# Sensor-amplification_V4.net
KiCad netlist of a schematic drawn in EAGLE
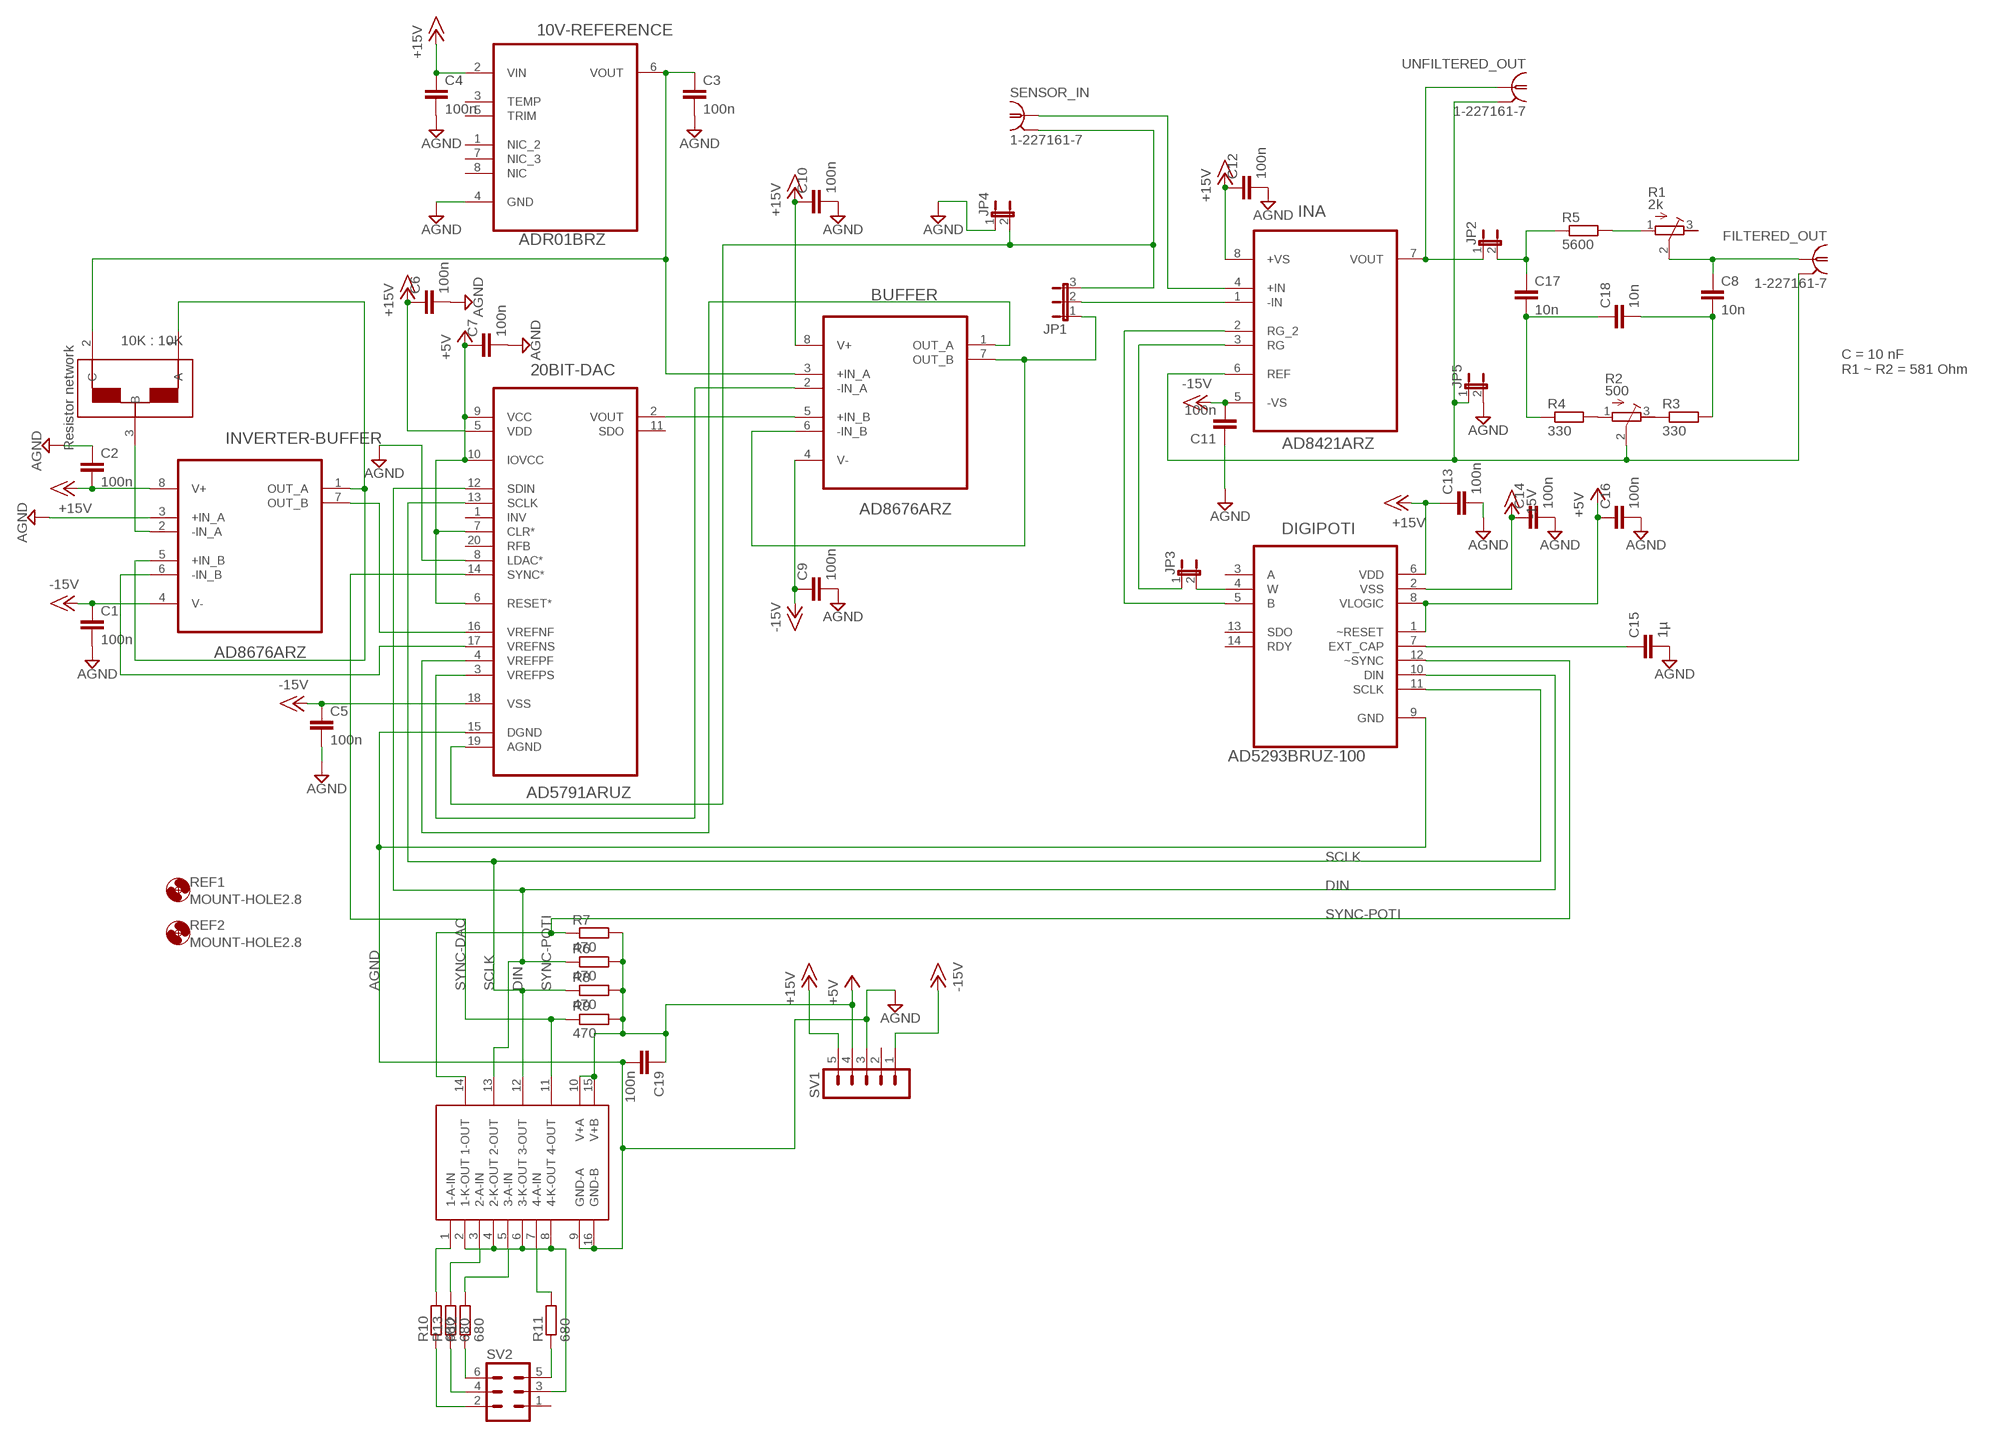
[diagram p0: schematic, sheet 1]

(export (version "E")
  (design (tool "Eeschema 10.0.6"))
  (components
    (comp (ref "10V-REFERENCE")
      (value "ADR01BRZ")
      (footprint "eagle-import:SOIC127P600X175-8N")
      (libsource (lib "eagle-import") (part "ADR01BRZ"))
    )
    (comp (ref "20BIT-DAC")
      (value "AD5791ARUZ")
      (footprint "eagle-import:SOP65P640X120-20N")
      (libsource (lib "eagle-import") (part "AD5791ARUZ"))
    )
    (comp (ref "BUFFER")
      (value "AD8676ARZ")
      (footprint "eagle-import:SOIC127P600X175-8N")
      (libsource (lib "eagle-import") (part "AD8676ARZ"))
    )
    (comp (ref "C1")
      (value "100n")
      (footprint "eagle-import:C0603")
      (libsource (lib "eagle-import") (part "C-EUC0603"))
    )
    (comp (ref "C2")
      (value "100n")
      (footprint "eagle-import:C0603")
      (libsource (lib "eagle-import") (part "C-EUC0603"))
    )
    (comp (ref "C3")
      (value "100n")
      (footprint "eagle-import:C0603")
      (libsource (lib "eagle-import") (part "C-EUC0603"))
    )
    (comp (ref "C4")
      (value "100n")
      (footprint "eagle-import:C0603")
      (libsource (lib "eagle-import") (part "C-EUC0603"))
    )
    (comp (ref "C5")
      (value "100n")
      (footprint "eagle-import:C0603")
      (libsource (lib "eagle-import") (part "C-EUC0603"))
    )
    (comp (ref "C6")
      (value "100n")
      (footprint "eagle-import:C0603")
      (libsource (lib "eagle-import") (part "C-EUC0603"))
    )
    (comp (ref "C7")
      (value "100n")
      (footprint "eagle-import:C0603")
      (libsource (lib "eagle-import") (part "C-EUC0603"))
    )
    (comp (ref "C8")
      (value "10n")
      (footprint "eagle-import:C0805")
      (libsource (lib "eagle-import") (part "C-EUC0805"))
    )
    (comp (ref "C9")
      (value "100n")
      (footprint "eagle-import:C0603")
      (libsource (lib "eagle-import") (part "C-EUC0603"))
    )
    (comp (ref "C10")
      (value "100n")
      (footprint "eagle-import:C0603")
      (libsource (lib "eagle-import") (part "C-EUC0603"))
    )
    (comp (ref "C11")
      (value "100n")
      (footprint "eagle-import:C0603")
      (libsource (lib "eagle-import") (part "C-EUC0603"))
    )
    (comp (ref "C12")
      (value "100n")
      (footprint "eagle-import:C0603")
      (libsource (lib "eagle-import") (part "C-EUC0603"))
    )
    (comp (ref "C13")
      (value "100n")
      (footprint "eagle-import:C0603")
      (libsource (lib "eagle-import") (part "C-EUC0603"))
    )
    (comp (ref "C14")
      (value "100n")
      (footprint "eagle-import:C0603")
      (libsource (lib "eagle-import") (part "C-EUC0603"))
    )
    (comp (ref "C15")
      (value "1µ")
      (footprint "eagle-import:C0603")
      (libsource (lib "eagle-import") (part "C-EUC0603"))
    )
    (comp (ref "C16")
      (value "100n")
      (footprint "eagle-import:C0603")
      (libsource (lib "eagle-import") (part "C-EUC0603"))
    )
    (comp (ref "C17")
      (value "10n")
      (footprint "eagle-import:C0805")
      (libsource (lib "eagle-import") (part "C-EUC0805"))
    )
    (comp (ref "C18")
      (value "10n")
      (footprint "eagle-import:C0805")
      (libsource (lib "eagle-import") (part "C-EUC0805"))
    )
    (comp (ref "C19")
      (value "100n")
      (footprint "eagle-import:C0603")
      (libsource (lib "eagle-import") (part "C-EUC0603"))
    )
    (comp (ref "DIGIPOTI")
      (value "AD5293BRUZ-100")
      (footprint "eagle-import:SOP65P640X120-14N")
      (libsource (lib "eagle-import") (part "AD5293BRUZ-100"))
    )
    (comp (ref "FILTERED_OUT")
      (value "1-227161-7")
      (footprint "eagle-import:AMP_227161")
      (fields (field (name "MF") "TYCO ELECTRONICS"))
      (libsource (lib "eagle-import") (part "?2271611--7"))
    )
    (comp (ref "INA")
      (value "AD8421ARZ")
      (footprint "eagle-import:SOIC127P600X175-8N")
      (libsource (lib "eagle-import") (part "AD8421ARZ"))
    )
    (comp (ref "INVERTER-BUFFER")
      (value "AD8676ARZ")
      (footprint "eagle-import:SOIC127P600X175-8N")
      (libsource (lib "eagle-import") (part "AD8676ARZ"))
    )
    (comp (ref "JP1")
      (value "JP2E")
      (footprint "eagle-import:JP2")
      (libsource (lib "eagle-import") (part "JP2E"))
    )
    (comp (ref "JP2")
      (value "JP1E")
      (footprint "eagle-import:JP1")
      (libsource (lib "eagle-import") (part "JP1E"))
    )
    (comp (ref "JP3")
      (value "JP1E")
      (footprint "eagle-import:JP1")
      (libsource (lib "eagle-import") (part "JP1E"))
    )
    (comp (ref "JP4")
      (value "JP1E")
      (footprint "eagle-import:JP1")
      (libsource (lib "eagle-import") (part "JP1E"))
    )
    (comp (ref "JP5")
      (value "JP1E")
      (footprint "eagle-import:JP1")
      (libsource (lib "eagle-import") (part "JP1E"))
    )
    (comp (ref "OPTOCOUPLER")
      (value "ACSL-6400")
      (footprint "eagle-import:SO16")
      (libsource (lib "eagle-import") (part "ACSL-6400"))
    )
    (comp (ref "R1")
      (value "2k")
      (footprint "eagle-import:RTRIM64W")
      (libsource (lib "eagle-import") (part "R-TRIMM64W"))
    )
    (comp (ref "R2")
      (value "500")
      (footprint "eagle-import:RTRIM64W")
      (libsource (lib "eagle-import") (part "R-TRIMM64W"))
    )
    (comp (ref "R3")
      (value "330")
      (footprint "eagle-import:M1206")
      (libsource (lib "eagle-import") (part "R-EU_M1206"))
    )
    (comp (ref "R4")
      (value "330")
      (footprint "eagle-import:M1206")
      (libsource (lib "eagle-import") (part "R-EU_M1206"))
    )
    (comp (ref "R5")
      (value "5600")
      (footprint "eagle-import:M1206")
      (libsource (lib "eagle-import") (part "R-EU_M1206"))
    )
    (comp (ref "R6")
      (value "470")
      (footprint "eagle-import:M1206")
      (libsource (lib "eagle-import") (part "R-EU_M1206"))
    )
    (comp (ref "R7")
      (value "470")
      (footprint "eagle-import:M1206")
      (libsource (lib "eagle-import") (part "R-EU_M1206"))
    )
    (comp (ref "R8")
      (value "470")
      (footprint "eagle-import:M1206")
      (libsource (lib "eagle-import") (part "R-EU_M1206"))
    )
    (comp (ref "R9")
      (value "470")
      (footprint "eagle-import:M1206")
      (libsource (lib "eagle-import") (part "R-EU_M1206"))
    )
    (comp (ref "R10")
      (value "680")
      (footprint "eagle-import:M1206")
      (libsource (lib "eagle-import") (part "R-EU_M1206"))
    )
    (comp (ref "R11")
      (value "680")
      (footprint "eagle-import:M1206")
      (libsource (lib "eagle-import") (part "R-EU_M1206"))
    )
    (comp (ref "R12")
      (value "680")
      (footprint "eagle-import:M1206")
      (libsource (lib "eagle-import") (part "R-EU_M1206"))
    )
    (comp (ref "R13")
      (value "680")
      (footprint "eagle-import:M1206")
      (libsource (lib "eagle-import") (part "R-EU_M1206"))
    )
    (comp (ref "R20")
      (value "MPMT2001AT5")
      (footprint "eagle-import:SOT23")
      (libsource (lib "eagle-import") (part "MPMT2001AT5"))
    )
    (comp (ref "REF1")
      (value "MOUNT-HOLE2.8")
      (footprint "eagle-import:2,8")
      (libsource (lib "eagle-import") (part "MOUNT-HOLE2.8"))
    )
    (comp (ref "REF2")
      (value "MOUNT-HOLE2.8")
      (footprint "eagle-import:2,8")
      (libsource (lib "eagle-import") (part "MOUNT-HOLE2.8"))
    )
    (comp (ref "SENSOR_IN")
      (value "1-227161-7")
      (footprint "eagle-import:AMP_227161")
      (fields (field (name "MF") "TYCO ELECTRONICS"))
      (libsource (lib "eagle-import") (part "?2271611--7"))
    )
    (comp (ref "SV1")
      (value "MA05-1")
      (footprint "eagle-import:MA05-1")
      (libsource (lib "eagle-import") (part "MA05-1"))
    )
    (comp (ref "SV2")
      (value "MA03-2")
      (footprint "eagle-import:MA03-2")
      (libsource (lib "eagle-import") (part "MA03-2"))
    )
    (comp (ref "UNFILTERED_OUT")
      (value "1-227161-7")
      (footprint "eagle-import:AMP_227161")
      (fields (field (name "MF") "TYCO ELECTRONICS"))
      (libsource (lib "eagle-import") (part "?2271611--7"))
    )
  )
  (nets
    (net (code "1") (name "+5V") (class "Default")
      (node (ref "20BIT-DAC") (pin "10") (pinfunction "IOVCC_10") (pintype "power_in"))
      (node (ref "20BIT-DAC") (pin "6") (pinfunction "RESET*_6") (pintype "input"))
      (node (ref "20BIT-DAC") (pin "7") (pinfunction "CLR*_7") (pintype "input"))
      (node (ref "20BIT-DAC") (pin "9") (pinfunction "VCC_9") (pintype "power_in"))
      (node (ref "C16") (pin "1") (pinfunction "1_1") (pintype "passive"))
      (node (ref "C19") (pin "1") (pinfunction "1_1") (pintype "passive"))
      (node (ref "C7") (pin "1") (pinfunction "1_1") (pintype "passive"))
      (node (ref "DIGIPOTI") (pin "1") (pinfunction "~{RESET}_1") (pintype "input"))
      (node (ref "DIGIPOTI") (pin "8") (pinfunction "VLOGIC_8") (pintype "power_in"))
      (node (ref "OPTOCOUPLER") (pin "10") (pinfunction "V+A_10") (pintype "power_in"))
      (node (ref "OPTOCOUPLER") (pin "15") (pinfunction "V+B_15") (pintype "power_in"))
      (node (ref "R6") (pin "2") (pinfunction "2_2") (pintype "passive"))
      (node (ref "R7") (pin "2") (pinfunction "2_2") (pintype "passive"))
      (node (ref "R8") (pin "2") (pinfunction "2_2") (pintype "passive"))
      (node (ref "R9") (pin "2") (pinfunction "2_2") (pintype "passive"))
      (node (ref "SV1") (pin "4") (pinfunction "4_4") (pintype "passive"))
    )
    (net (code "2") (name "+15V") (class "Default")
      (node (ref "10V-REFERENCE") (pin "2") (pinfunction "VIN_2") (pintype "input"))
      (node (ref "20BIT-DAC") (pin "5") (pinfunction "VDD_5") (pintype "power_in"))
      (node (ref "BUFFER") (pin "8") (pinfunction "V+_8") (pintype "power_in"))
      (node (ref "C10") (pin "1") (pinfunction "1_1") (pintype "passive"))
      (node (ref "C12") (pin "1") (pinfunction "1_1") (pintype "passive"))
      (node (ref "C13") (pin "1") (pinfunction "1_1") (pintype "passive"))
      (node (ref "C2") (pin "2") (pinfunction "2_2") (pintype "passive"))
      (node (ref "C4") (pin "1") (pinfunction "1_1") (pintype "passive"))
      (node (ref "C6") (pin "1") (pinfunction "1_1") (pintype "passive"))
      (node (ref "DIGIPOTI") (pin "6") (pinfunction "VDD_6") (pintype "power_in"))
      (node (ref "INA") (pin "8") (pinfunction "+VS_8") (pintype "power_in"))
      (node (ref "INVERTER-BUFFER") (pin "8") (pinfunction "V+_8") (pintype "power_in"))
      (node (ref "SV1") (pin "5") (pinfunction "5_5") (pintype "passive"))
    )
    (net (code "3") (name "-15V") (class "Default")
      (node (ref "20BIT-DAC") (pin "18") (pinfunction "VSS_18") (pintype "power_in"))
      (node (ref "BUFFER") (pin "4") (pinfunction "V-_4") (pintype "power_in"))
      (node (ref "C1") (pin "1") (pinfunction "1_1") (pintype "passive"))
      (node (ref "C11") (pin "2") (pinfunction "2_2") (pintype "passive"))
      (node (ref "C14") (pin "1") (pinfunction "1_1") (pintype "passive"))
      (node (ref "C5") (pin "1") (pinfunction "1_1") (pintype "passive"))
      (node (ref "C9") (pin "1") (pinfunction "1_1") (pintype "passive"))
      (node (ref "DIGIPOTI") (pin "2") (pinfunction "VSS_2") (pintype "power_in"))
      (node (ref "INA") (pin "5") (pinfunction "-VS_5") (pintype "power_in"))
      (node (ref "INVERTER-BUFFER") (pin "4") (pinfunction "V-_4") (pintype "power_in"))
      (node (ref "SV1") (pin "1") (pinfunction "1_1") (pintype "passive"))
    )
    (net (code "4") (name "/DIN") (class "Default")
      (node (ref "20BIT-DAC") (pin "12") (pinfunction "SDIN_12") (pintype "input"))
      (node (ref "DIGIPOTI") (pin "10") (pinfunction "DIN_10") (pintype "input"))
      (node (ref "OPTOCOUPLER") (pin "13") (pinfunction "2-OUT_13") (pintype "output"))
      (node (ref "R6") (pin "1") (pinfunction "1_1") (pintype "passive"))
    )
    (net (code "5") (name "/SCLK") (class "Default")
      (node (ref "20BIT-DAC") (pin "13") (pinfunction "SCLK_13") (pintype "input"))
      (node (ref "DIGIPOTI") (pin "11") (pinfunction "SCLK_11") (pintype "input"))
      (node (ref "OPTOCOUPLER") (pin "12") (pinfunction "3-OUT_12") (pintype "output"))
      (node (ref "R8") (pin "1") (pinfunction "1_1") (pintype "passive"))
    )
    (net (code "6") (name "/SYNC-DAC") (class "Default")
      (node (ref "20BIT-DAC") (pin "14") (pinfunction "SYNC*_14") (pintype "input"))
      (node (ref "OPTOCOUPLER") (pin "11") (pinfunction "4-OUT_11") (pintype "output"))
      (node (ref "R9") (pin "1") (pinfunction "1_1") (pintype "passive"))
    )
    (net (code "7") (name "/SYNC-POTI") (class "Default")
      (node (ref "DIGIPOTI") (pin "12") (pinfunction "~{SYNC}_12") (pintype "input"))
      (node (ref "OPTOCOUPLER") (pin "14") (pinfunction "1-OUT_14") (pintype "output"))
      (node (ref "R7") (pin "1") (pinfunction "1_1") (pintype "passive"))
    )
    (net (code "8") (name "AGND") (class "Default")
      (node (ref "10V-REFERENCE") (pin "4") (pinfunction "GND_4") (pintype "passive"))
      (node (ref "20BIT-DAC") (pin "15") (pinfunction "DGND_15") (pintype "passive"))
      (node (ref "20BIT-DAC") (pin "8") (pinfunction "LDAC*_8") (pintype "input"))
      (node (ref "C1") (pin "2") (pinfunction "2_2") (pintype "passive"))
      (node (ref "C10") (pin "2") (pinfunction "2_2") (pintype "passive"))
      (node (ref "C11") (pin "1") (pinfunction "1_1") (pintype "passive"))
      (node (ref "C12") (pin "2") (pinfunction "2_2") (pintype "passive"))
      (node (ref "C13") (pin "2") (pinfunction "2_2") (pintype "passive"))
      (node (ref "C14") (pin "2") (pinfunction "2_2") (pintype "passive"))
      (node (ref "C15") (pin "2") (pinfunction "2_2") (pintype "passive"))
      (node (ref "C16") (pin "2") (pinfunction "2_2") (pintype "passive"))
      (node (ref "C19") (pin "2") (pinfunction "2_2") (pintype "passive"))
      (node (ref "C2") (pin "1") (pinfunction "1_1") (pintype "passive"))
      (node (ref "C3") (pin "2") (pinfunction "2_2") (pintype "passive"))
      (node (ref "C4") (pin "2") (pinfunction "2_2") (pintype "passive"))
      (node (ref "C5") (pin "2") (pinfunction "2_2") (pintype "passive"))
      (node (ref "C6") (pin "2") (pinfunction "2_2") (pintype "passive"))
      (node (ref "C7") (pin "2") (pinfunction "2_2") (pintype "passive"))
      (node (ref "C9") (pin "2") (pinfunction "2_2") (pintype "passive"))
      (node (ref "DIGIPOTI") (pin "9") (pinfunction "GND_9") (pintype "passive"))
      (node (ref "INVERTER-BUFFER") (pin "3") (pinfunction "+IN_A_3") (pintype "input"))
      (node (ref "JP4") (pin "1") (pinfunction "1_1") (pintype "passive"))
      (node (ref "JP5") (pin "2") (pinfunction "2_2") (pintype "passive"))
      (node (ref "OPTOCOUPLER") (pin "16") (pinfunction "GND-B_16") (pintype "power_in"))
      (node (ref "OPTOCOUPLER") (pin "9") (pinfunction "GND-A_9") (pintype "power_in"))
      (node (ref "SV1") (pin "3") (pinfunction "3_3") (pintype "passive"))
    )
    (net (code "9") (name "Net-(10V-REFERENCE-VOUT)") (class "Default")
      (node (ref "10V-REFERENCE") (pin "6") (pinfunction "VOUT_6") (pintype "output"))
      (node (ref "BUFFER") (pin "3") (pinfunction "+IN_A_3") (pintype "input"))
      (node (ref "C3") (pin "1") (pinfunction "1_1") (pintype "passive"))
      (node (ref "R20") (pin "2") (pinfunction "C_2") (pintype "passive"))
    )
    (net (code "10") (name "Net-(20BIT-DAC-AGND)") (class "Default")
      (node (ref "20BIT-DAC") (pin "19") (pinfunction "AGND_19") (pintype "passive"))
      (node (ref "JP1") (pin "3") (pinfunction "3_3") (pintype "passive"))
      (node (ref "JP4") (pin "2") (pinfunction "2_2") (pintype "passive"))
      (node (ref "SENSOR_IN") (pin "2") (pinfunction "2_2") (pintype "passive"))
    )
    (net (code "11") (name "Net-(20BIT-DAC-VOUT)") (class "Default")
      (node (ref "20BIT-DAC") (pin "2") (pinfunction "VOUT_2") (pintype "output"))
      (node (ref "BUFFER") (pin "5") (pinfunction "+IN_B_5") (pintype "input"))
    )
    (net (code "12") (name "Net-(20BIT-DAC-VREFNF)") (class "Default")
      (node (ref "20BIT-DAC") (pin "16") (pinfunction "VREFNF_16") (pintype "input"))
      (node (ref "INVERTER-BUFFER") (pin "7") (pinfunction "OUT_B_7") (pintype "output"))
    )
    (net (code "13") (name "Net-(20BIT-DAC-VREFNS)") (class "Default")
      (node (ref "20BIT-DAC") (pin "17") (pinfunction "VREFNS_17") (pintype "input"))
      (node (ref "INVERTER-BUFFER") (pin "6") (pinfunction "-IN_B_6") (pintype "input"))
    )
    (net (code "14") (name "Net-(20BIT-DAC-VREFPF)") (class "Default")
      (node (ref "20BIT-DAC") (pin "4") (pinfunction "VREFPF_4") (pintype "input"))
      (node (ref "BUFFER") (pin "1") (pinfunction "OUT_A_1") (pintype "output"))
    )
    (net (code "15") (name "Net-(20BIT-DAC-VREFPS)") (class "Default")
      (node (ref "20BIT-DAC") (pin "3") (pinfunction "VREFPS_3") (pintype "input"))
      (node (ref "BUFFER") (pin "2") (pinfunction "-IN_A_2") (pintype "input"))
    )
    (net (code "16") (name "Net-(BUFFER--IN_B)") (class "Default")
      (node (ref "BUFFER") (pin "6") (pinfunction "-IN_B_6") (pintype "input"))
      (node (ref "BUFFER") (pin "7") (pinfunction "OUT_B_7") (pintype "output"))
      (node (ref "JP1") (pin "1") (pinfunction "1_1") (pintype "passive"))
    )
    (net (code "17") (name "Net-(C17-Pad1)") (class "Default")
      (node (ref "C17") (pin "1") (pinfunction "1_1") (pintype "passive"))
      (node (ref "JP2") (pin "2") (pinfunction "2_2") (pintype "passive"))
      (node (ref "R5") (pin "1") (pinfunction "1_1") (pintype "passive"))
    )
    (net (code "18") (name "Net-(C17-Pad2)") (class "Default")
      (node (ref "C17") (pin "2") (pinfunction "2_2") (pintype "passive"))
      (node (ref "C18") (pin "1") (pinfunction "1_1") (pintype "passive"))
      (node (ref "R4") (pin "1") (pinfunction "1_1") (pintype "passive"))
    )
    (net (code "19") (name "Net-(C18-Pad2)") (class "Default")
      (node (ref "C18") (pin "2") (pinfunction "2_2") (pintype "passive"))
      (node (ref "C8") (pin "2") (pinfunction "2_2") (pintype "passive"))
      (node (ref "R3") (pin "2") (pinfunction "2_2") (pintype "passive"))
    )
    (net (code "20") (name "Net-(DIGIPOTI-B)") (class "Default")
      (node (ref "DIGIPOTI") (pin "5") (pinfunction "B_5") (pintype "passive"))
      (node (ref "INA") (pin "2") (pinfunction "RG_2_2") (pintype "input"))
    )
    (net (code "21") (name "Net-(DIGIPOTI-EXT_CAP)") (class "Default")
      (node (ref "C15") (pin "1") (pinfunction "1_1") (pintype "passive"))
      (node (ref "DIGIPOTI") (pin "7") (pinfunction "EXT_CAP_7") (pintype "passive"))
    )
    (net (code "22") (name "Net-(DIGIPOTI-W)") (class "Default")
      (node (ref "DIGIPOTI") (pin "4") (pinfunction "W_4") (pintype "passive"))
      (node (ref "JP3") (pin "2") (pinfunction "2_2") (pintype "passive"))
    )
    (net (code "23") (name "Net-(INA-+IN)") (class "Default")
      (node (ref "INA") (pin "4") (pinfunction "+IN_4") (pintype "input"))
      (node (ref "SENSOR_IN") (pin "1") (pinfunction "1_1") (pintype "passive"))
    )
    (net (code "24") (name "Net-(INA--IN)") (class "Default")
      (node (ref "INA") (pin "1") (pinfunction "-IN_1") (pintype "input"))
      (node (ref "JP1") (pin "2") (pinfunction "2_2") (pintype "passive"))
    )
    (net (code "25") (name "Net-(INA-REF)") (class "Default")
      (node (ref "FILTERED_OUT") (pin "2") (pinfunction "2_2") (pintype "passive"))
      (node (ref "INA") (pin "6") (pinfunction "REF_6") (pintype "input"))
      (node (ref "JP5") (pin "1") (pinfunction "1_1") (pintype "passive"))
      (node (ref "R2") (pin "2") (pinfunction "S_2") (pintype "passive"))
      (node (ref "UNFILTERED_OUT") (pin "2") (pinfunction "2_2") (pintype "passive"))
    )
    (net (code "26") (name "Net-(INA-RG)") (class "Default")
      (node (ref "INA") (pin "3") (pinfunction "RG_3") (pintype "input"))
      (node (ref "JP3") (pin "1") (pinfunction "1_1") (pintype "passive"))
    )
    (net (code "27") (name "Net-(INA-VOUT)") (class "Default")
      (node (ref "INA") (pin "7") (pinfunction "VOUT_7") (pintype "output"))
      (node (ref "JP2") (pin "1") (pinfunction "1_1") (pintype "passive"))
      (node (ref "UNFILTERED_OUT") (pin "1") (pinfunction "1_1") (pintype "passive"))
    )
    (net (code "28") (name "Net-(INVERTER-BUFFER-+IN_B)") (class "Default")
      (node (ref "INVERTER-BUFFER") (pin "1") (pinfunction "OUT_A_1") (pintype "output"))
      (node (ref "INVERTER-BUFFER") (pin "5") (pinfunction "+IN_B_5") (pintype "input"))
      (node (ref "R20") (pin "1") (pinfunction "A_1") (pintype "passive"))
    )
    (net (code "29") (name "Net-(INVERTER-BUFFER--IN_A)") (class "Default")
      (node (ref "INVERTER-BUFFER") (pin "2") (pinfunction "-IN_A_2") (pintype "input"))
      (node (ref "R20") (pin "3") (pinfunction "B_3") (pintype "passive"))
    )
    (net (code "30") (name "Net-(OPTOCOUPLER-1-A-IN)") (class "Default")
      (node (ref "OPTOCOUPLER") (pin "1") (pinfunction "1-A-IN_1") (pintype "input"))
      (node (ref "R10") (pin "2") (pinfunction "2_2") (pintype "passive"))
    )
    (net (code "31") (name "Net-(OPTOCOUPLER-1-K-OUT)") (class "Default")
      (node (ref "OPTOCOUPLER") (pin "2") (pinfunction "1-K-OUT_2") (pintype "output"))
      (node (ref "OPTOCOUPLER") (pin "4") (pinfunction "2-K-OUT_4") (pintype "output"))
      (node (ref "OPTOCOUPLER") (pin "6") (pinfunction "3-K-OUT_6") (pintype "output"))
      (node (ref "OPTOCOUPLER") (pin "8") (pinfunction "4-K-OUT_8") (pintype "output"))
      (node (ref "SV2") (pin "3") (pinfunction "3_3") (pintype "passive"))
    )
    (net (code "32") (name "Net-(OPTOCOUPLER-2-A-IN)") (class "Default")
      (node (ref "OPTOCOUPLER") (pin "3") (pinfunction "2-A-IN_3") (pintype "input"))
      (node (ref "R13") (pin "2") (pinfunction "2_2") (pintype "passive"))
    )
    (net (code "33") (name "Net-(OPTOCOUPLER-3-A-IN)") (class "Default")
      (node (ref "OPTOCOUPLER") (pin "5") (pinfunction "3-A-IN_5") (pintype "input"))
      (node (ref "R12") (pin "2") (pinfunction "2_2") (pintype "passive"))
    )
    (net (code "34") (name "Net-(OPTOCOUPLER-4-A-IN)") (class "Default")
      (node (ref "OPTOCOUPLER") (pin "7") (pinfunction "4-A-IN_7") (pintype "input"))
      (node (ref "R11") (pin "2") (pinfunction "2_2") (pintype "passive"))
    )
    (net (code "35") (name "Net-(R1-A)") (class "Default")
      (node (ref "R1") (pin "1") (pinfunction "A_1") (pintype "passive"))
      (node (ref "R5") (pin "2") (pinfunction "2_2") (pintype "passive"))
    )
    (net (code "36") (name "Net-(R1-S)") (class "Default")
      (node (ref "C8") (pin "1") (pinfunction "1_1") (pintype "passive"))
      (node (ref "FILTERED_OUT") (pin "1") (pinfunction "1_1") (pintype "passive"))
      (node (ref "R1") (pin "2") (pinfunction "S_2") (pintype "passive"))
    )
    (net (code "37") (name "Net-(R2-A)") (class "Default")
      (node (ref "R2") (pin "1") (pinfunction "A_1") (pintype "passive"))
      (node (ref "R4") (pin "2") (pinfunction "2_2") (pintype "passive"))
    )
    (net (code "38") (name "Net-(R2-E)") (class "Default")
      (node (ref "R2") (pin "3") (pinfunction "E_3") (pintype "passive"))
      (node (ref "R3") (pin "1") (pinfunction "1_1") (pintype "passive"))
    )
    (net (code "39") (name "Net-(R10-Pad1)") (class "Default")
      (node (ref "R10") (pin "1") (pinfunction "1_1") (pintype "passive"))
      (node (ref "SV2") (pin "2") (pinfunction "2_2") (pintype "passive"))
    )
    (net (code "40") (name "Net-(R11-Pad1)") (class "Default")
      (node (ref "R11") (pin "1") (pinfunction "1_1") (pintype "passive"))
      (node (ref "SV2") (pin "5") (pinfunction "5_5") (pintype "passive"))
    )
    (net (code "41") (name "Net-(R12-Pad1)") (class "Default")
      (node (ref "R12") (pin "1") (pinfunction "1_1") (pintype "passive"))
      (node (ref "SV2") (pin "6") (pinfunction "6_6") (pintype "passive"))
    )
    (net (code "42") (name "Net-(R13-Pad1)") (class "Default")
      (node (ref "R13") (pin "1") (pinfunction "1_1") (pintype "passive"))
      (node (ref "SV2") (pin "4") (pinfunction "4_4") (pintype "passive"))
    )
    (net (code "43") (name "unconnected-(10V-REFERENCE-NIC-Pad8)") (class "Default")
      (node (ref "10V-REFERENCE") (pin "8") (pinfunction "NIC_8") (pintype "no_connect"))
    )
    (net (code "44") (name "unconnected-(10V-REFERENCE-NIC_2-Pad1)") (class "Default")
      (node (ref "10V-REFERENCE") (pin "1") (pinfunction "NIC_2_1") (pintype "no_connect"))
    )
    (net (code "45") (name "unconnected-(10V-REFERENCE-NIC_3-Pad7)") (class "Default")
      (node (ref "10V-REFERENCE") (pin "7") (pinfunction "NIC_3_7") (pintype "no_connect"))
    )
    (net (code "46") (name "unconnected-(10V-REFERENCE-TEMP-Pad3)") (class "Default")
      (node (ref "10V-REFERENCE") (pin "3") (pinfunction "TEMP_3") (pintype "passive"))
    )
    (net (code "47") (name "unconnected-(10V-REFERENCE-TRIM-Pad5)") (class "Default")
      (node (ref "10V-REFERENCE") (pin "5") (pinfunction "TRIM_5") (pintype "passive"))
    )
    (net (code "48") (name "unconnected-(20BIT-DAC-INV-Pad1)") (class "Default")
      (node (ref "20BIT-DAC") (pin "1") (pinfunction "INV_1") (pintype "input"))
    )
    (net (code "49") (name "unconnected-(20BIT-DAC-RFB-Pad20)") (class "Default")
      (node (ref "20BIT-DAC") (pin "20") (pinfunction "RFB_20") (pintype "passive"))
    )
    (net (code "50") (name "unconnected-(20BIT-DAC-SDO-Pad11)") (class "Default")
      (node (ref "20BIT-DAC") (pin "11") (pinfunction "SDO_11") (pintype "output"))
    )
    (net (code "51") (name "unconnected-(DIGIPOTI-A-Pad3)") (class "Default")
      (node (ref "DIGIPOTI") (pin "3") (pinfunction "A_3") (pintype "passive"))
    )
    (net (code "52") (name "unconnected-(DIGIPOTI-RDY-Pad14)") (class "Default")
      (node (ref "DIGIPOTI") (pin "14") (pinfunction "RDY_14") (pintype "output"))
    )
    (net (code "53") (name "unconnected-(DIGIPOTI-SDO-Pad13)") (class "Default")
      (node (ref "DIGIPOTI") (pin "13") (pinfunction "SDO_13") (pintype "output"))
    )
    (net (code "54") (name "unconnected-(R1-E-Pad3)") (class "Default")
      (node (ref "R1") (pin "3") (pinfunction "E_3") (pintype "passive"))
    )
    (net (code "55") (name "unconnected-(SV1-Pad2)") (class "Default")
      (node (ref "SV1") (pin "2") (pinfunction "2_2") (pintype "passive"))
    )
    (net (code "56") (name "unconnected-(SV2-Pad1)") (class "Default")
      (node (ref "SV2") (pin "1") (pinfunction "1_1") (pintype "passive"))
    )
  )
)
